# flatsat.net
KiCad netlist of a schematic drawn in EAGLE
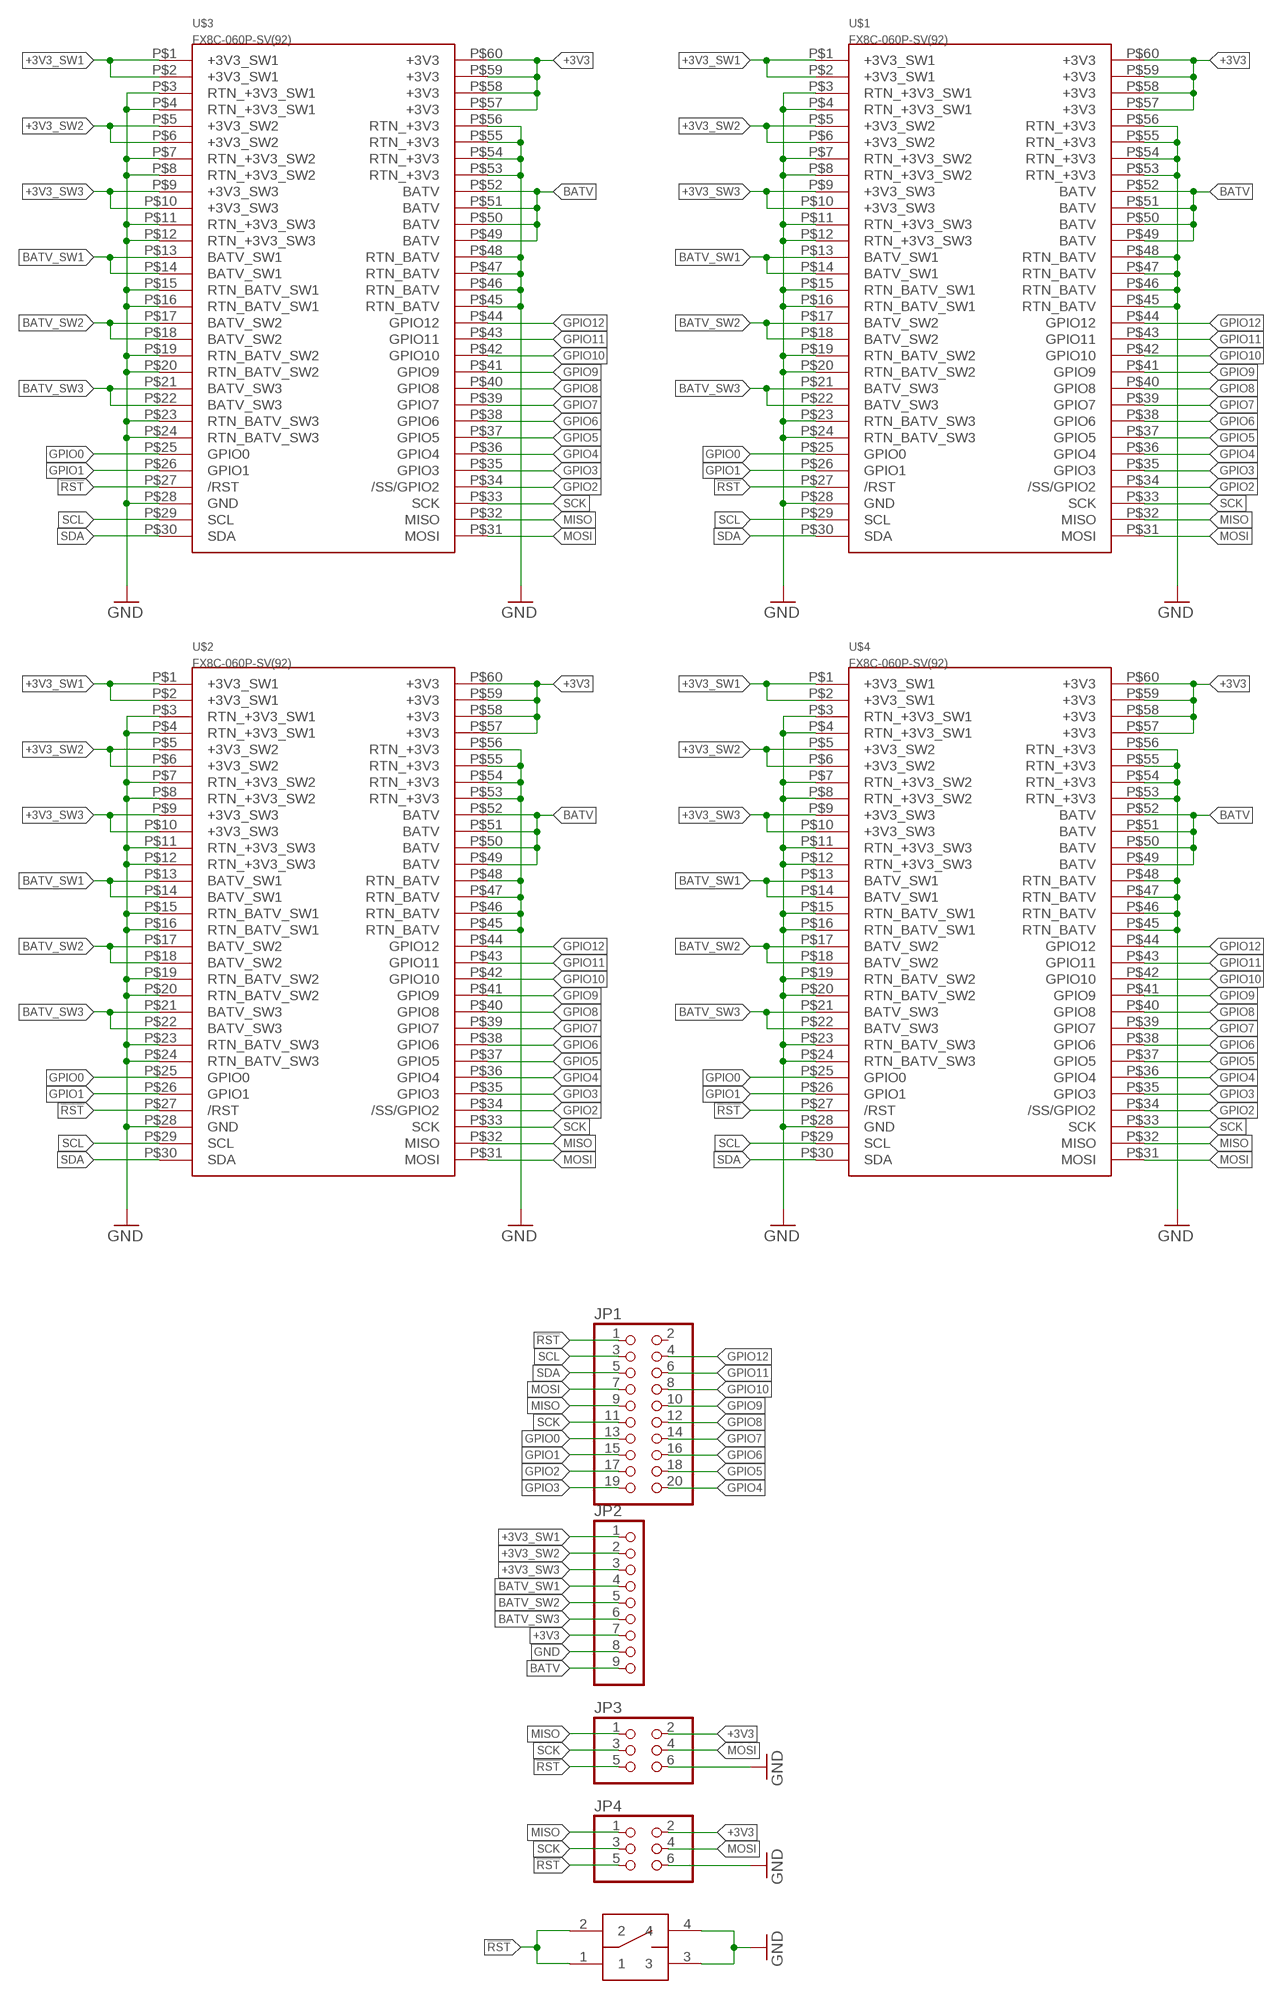
[diagram p0: schematic, sheet 1]

(export (version "E")
  (design (tool "Eeschema 10.0.6"))
  (components
    (comp (ref "JP1")
      (value "PINHD-2X10")
      (footprint "eagle-import:2X10")
      (libsource (lib "eagle-import") (part "PINHD-2X10"))
    )
    (comp (ref "JP2")
      (value "PINHD-1X9")
      (footprint "eagle-import:1X09")
      (libsource (lib "eagle-import") (part "PINHD-1X9"))
    )
    (comp (ref "JP3")
      (value "PINHD-2X3")
      (footprint "eagle-import:2X03")
      (libsource (lib "eagle-import") (part "PINHD-2X3"))
    )
    (comp (ref "JP4")
      (value "PINHD-2X3")
      (footprint "eagle-import:2X03")
      (libsource (lib "eagle-import") (part "PINHD-2X3"))
    )
    (comp (ref "U$1")
      (value "FX8C-060P-SV(92)")
      (footprint "eagle-import:FX8C-060P-SV(92)")
      (libsource (lib "eagle-import") (part "FX8C-060P-SV(92)"))
    )
    (comp (ref "U$2")
      (value "FX8C-060P-SV(92)")
      (footprint "eagle-import:FX8C-060P-SV(92)")
      (libsource (lib "eagle-import") (part "FX8C-060P-SV(92)"))
    )
    (comp (ref "U$3")
      (value "FX8C-060P-SV(92)")
      (footprint "eagle-import:FX8C-060P-SV(92)")
      (libsource (lib "eagle-import") (part "FX8C-060P-SV(92)"))
    )
    (comp (ref "U$4")
      (value "FX8C-060P-SV(92)")
      (footprint "eagle-import:FX8C-060P-SV(92)")
      (libsource (lib "eagle-import") (part "FX8C-060P-SV(92)"))
    )
    (comp (ref "U$5")
      (value "SWITCH-TL3301")
      (footprint "eagle-import:SWITCH-TL3301")
      (libsource (lib "eagle-import") (part "SWITCH-TL3301"))
    )
  )
  (nets
    (net (code "1") (name "+3V3") (class "Default")
      (node (ref "JP2") (pin "7") (pinfunction "7_7") (pintype "passive"))
      (node (ref "JP3") (pin "2") (pinfunction "2_2") (pintype "passive"))
      (node (ref "JP4") (pin "2") (pinfunction "2_2") (pintype "passive"))
      (node (ref "U$1") (pin "P$57") (pinfunction "+3V3_P$57") (pintype "power_in"))
      (node (ref "U$1") (pin "P$58") (pinfunction "+3V3_P$58") (pintype "power_in"))
      (node (ref "U$1") (pin "P$59") (pinfunction "+3V3_P$59") (pintype "power_in"))
      (node (ref "U$1") (pin "P$60") (pinfunction "+3V3_P$60") (pintype "power_in"))
      (node (ref "U$2") (pin "P$57") (pinfunction "+3V3_P$57") (pintype "power_in"))
      (node (ref "U$2") (pin "P$58") (pinfunction "+3V3_P$58") (pintype "power_in"))
      (node (ref "U$2") (pin "P$59") (pinfunction "+3V3_P$59") (pintype "power_in"))
      (node (ref "U$2") (pin "P$60") (pinfunction "+3V3_P$60") (pintype "power_in"))
      (node (ref "U$3") (pin "P$57") (pinfunction "+3V3_P$57") (pintype "power_in"))
      (node (ref "U$3") (pin "P$58") (pinfunction "+3V3_P$58") (pintype "power_in"))
      (node (ref "U$3") (pin "P$59") (pinfunction "+3V3_P$59") (pintype "power_in"))
      (node (ref "U$3") (pin "P$60") (pinfunction "+3V3_P$60") (pintype "power_in"))
      (node (ref "U$4") (pin "P$57") (pinfunction "+3V3_P$57") (pintype "power_in"))
      (node (ref "U$4") (pin "P$58") (pinfunction "+3V3_P$58") (pintype "power_in"))
      (node (ref "U$4") (pin "P$59") (pinfunction "+3V3_P$59") (pintype "power_in"))
      (node (ref "U$4") (pin "P$60") (pinfunction "+3V3_P$60") (pintype "power_in"))
    )
    (net (code "2") (name "+3V3_SW1") (class "Default")
      (node (ref "JP2") (pin "1") (pinfunction "1_1") (pintype "passive"))
      (node (ref "U$1") (pin "P$1") (pinfunction "+3V3_SW1_P$1") (pintype "power_in"))
      (node (ref "U$1") (pin "P$2") (pinfunction "+3V3_SW1_P$2") (pintype "power_in"))
      (node (ref "U$2") (pin "P$1") (pinfunction "+3V3_SW1_P$1") (pintype "power_in"))
      (node (ref "U$2") (pin "P$2") (pinfunction "+3V3_SW1_P$2") (pintype "power_in"))
      (node (ref "U$3") (pin "P$1") (pinfunction "+3V3_SW1_P$1") (pintype "power_in"))
      (node (ref "U$3") (pin "P$2") (pinfunction "+3V3_SW1_P$2") (pintype "power_in"))
      (node (ref "U$4") (pin "P$1") (pinfunction "+3V3_SW1_P$1") (pintype "power_in"))
      (node (ref "U$4") (pin "P$2") (pinfunction "+3V3_SW1_P$2") (pintype "power_in"))
    )
    (net (code "3") (name "+3V3_SW2") (class "Default")
      (node (ref "JP2") (pin "2") (pinfunction "2_2") (pintype "passive"))
      (node (ref "U$1") (pin "P$5") (pinfunction "+3V3_SW2_P$5") (pintype "power_in"))
      (node (ref "U$1") (pin "P$6") (pinfunction "+3V3_SW2_P$6") (pintype "power_in"))
      (node (ref "U$2") (pin "P$5") (pinfunction "+3V3_SW2_P$5") (pintype "power_in"))
      (node (ref "U$2") (pin "P$6") (pinfunction "+3V3_SW2_P$6") (pintype "power_in"))
      (node (ref "U$3") (pin "P$5") (pinfunction "+3V3_SW2_P$5") (pintype "power_in"))
      (node (ref "U$3") (pin "P$6") (pinfunction "+3V3_SW2_P$6") (pintype "power_in"))
      (node (ref "U$4") (pin "P$5") (pinfunction "+3V3_SW2_P$5") (pintype "power_in"))
      (node (ref "U$4") (pin "P$6") (pinfunction "+3V3_SW2_P$6") (pintype "power_in"))
    )
    (net (code "4") (name "+3V3_SW3") (class "Default")
      (node (ref "JP2") (pin "3") (pinfunction "3_3") (pintype "passive"))
      (node (ref "U$1") (pin "P$10") (pinfunction "+3V3_SW3_P$10") (pintype "power_in"))
      (node (ref "U$1") (pin "P$9") (pinfunction "+3V3_SW3_P$9") (pintype "power_in"))
      (node (ref "U$2") (pin "P$10") (pinfunction "+3V3_SW3_P$10") (pintype "power_in"))
      (node (ref "U$2") (pin "P$9") (pinfunction "+3V3_SW3_P$9") (pintype "power_in"))
      (node (ref "U$3") (pin "P$10") (pinfunction "+3V3_SW3_P$10") (pintype "power_in"))
      (node (ref "U$3") (pin "P$9") (pinfunction "+3V3_SW3_P$9") (pintype "power_in"))
      (node (ref "U$4") (pin "P$10") (pinfunction "+3V3_SW3_P$10") (pintype "power_in"))
      (node (ref "U$4") (pin "P$9") (pinfunction "+3V3_SW3_P$9") (pintype "power_in"))
    )
    (net (code "5") (name "/~{RST}") (class "Default")
      (node (ref "JP1") (pin "1") (pinfunction "1_1") (pintype "passive"))
      (node (ref "JP3") (pin "5") (pinfunction "5_5") (pintype "passive"))
      (node (ref "JP4") (pin "5") (pinfunction "5_5") (pintype "passive"))
      (node (ref "U$1") (pin "P$27") (pinfunction "/RST_P$27") (pintype "bidirectional"))
      (node (ref "U$2") (pin "P$27") (pinfunction "/RST_P$27") (pintype "bidirectional"))
      (node (ref "U$3") (pin "P$27") (pinfunction "/RST_P$27") (pintype "bidirectional"))
      (node (ref "U$4") (pin "P$27") (pinfunction "/RST_P$27") (pintype "bidirectional"))
      (node (ref "U$5") (pin "1") (pinfunction "1_1") (pintype "bidirectional"))
      (node (ref "U$5") (pin "2") (pinfunction "2_2") (pintype "bidirectional"))
    )
    (net (code "6") (name "BATV") (class "Default")
      (node (ref "JP2") (pin "9") (pinfunction "9_9") (pintype "passive"))
      (node (ref "U$1") (pin "P$49") (pinfunction "BATV_P$49") (pintype "power_in"))
      (node (ref "U$1") (pin "P$50") (pinfunction "BATV_P$50") (pintype "power_in"))
      (node (ref "U$1") (pin "P$51") (pinfunction "BATV_P$51") (pintype "power_in"))
      (node (ref "U$1") (pin "P$52") (pinfunction "BATV_P$52") (pintype "power_in"))
      (node (ref "U$2") (pin "P$49") (pinfunction "BATV_P$49") (pintype "power_in"))
      (node (ref "U$2") (pin "P$50") (pinfunction "BATV_P$50") (pintype "power_in"))
      (node (ref "U$2") (pin "P$51") (pinfunction "BATV_P$51") (pintype "power_in"))
      (node (ref "U$2") (pin "P$52") (pinfunction "BATV_P$52") (pintype "power_in"))
      (node (ref "U$3") (pin "P$49") (pinfunction "BATV_P$49") (pintype "power_in"))
      (node (ref "U$3") (pin "P$50") (pinfunction "BATV_P$50") (pintype "power_in"))
      (node (ref "U$3") (pin "P$51") (pinfunction "BATV_P$51") (pintype "power_in"))
      (node (ref "U$3") (pin "P$52") (pinfunction "BATV_P$52") (pintype "power_in"))
      (node (ref "U$4") (pin "P$49") (pinfunction "BATV_P$49") (pintype "power_in"))
      (node (ref "U$4") (pin "P$50") (pinfunction "BATV_P$50") (pintype "power_in"))
      (node (ref "U$4") (pin "P$51") (pinfunction "BATV_P$51") (pintype "power_in"))
      (node (ref "U$4") (pin "P$52") (pinfunction "BATV_P$52") (pintype "power_in"))
    )
    (net (code "7") (name "BATV_SW1") (class "Default")
      (node (ref "JP2") (pin "4") (pinfunction "4_4") (pintype "passive"))
      (node (ref "U$1") (pin "P$13") (pinfunction "BATV_SW1_P$13") (pintype "power_in"))
      (node (ref "U$1") (pin "P$14") (pinfunction "BATV_SW1_P$14") (pintype "power_in"))
      (node (ref "U$2") (pin "P$13") (pinfunction "BATV_SW1_P$13") (pintype "power_in"))
      (node (ref "U$2") (pin "P$14") (pinfunction "BATV_SW1_P$14") (pintype "power_in"))
      (node (ref "U$3") (pin "P$13") (pinfunction "BATV_SW1_P$13") (pintype "power_in"))
      (node (ref "U$3") (pin "P$14") (pinfunction "BATV_SW1_P$14") (pintype "power_in"))
      (node (ref "U$4") (pin "P$13") (pinfunction "BATV_SW1_P$13") (pintype "power_in"))
      (node (ref "U$4") (pin "P$14") (pinfunction "BATV_SW1_P$14") (pintype "power_in"))
    )
    (net (code "8") (name "BATV_SW2") (class "Default")
      (node (ref "JP2") (pin "5") (pinfunction "5_5") (pintype "passive"))
      (node (ref "U$1") (pin "P$17") (pinfunction "BATV_SW2_P$17") (pintype "power_in"))
      (node (ref "U$1") (pin "P$18") (pinfunction "BATV_SW2_P$18") (pintype "power_in"))
      (node (ref "U$2") (pin "P$17") (pinfunction "BATV_SW2_P$17") (pintype "power_in"))
      (node (ref "U$2") (pin "P$18") (pinfunction "BATV_SW2_P$18") (pintype "power_in"))
      (node (ref "U$3") (pin "P$17") (pinfunction "BATV_SW2_P$17") (pintype "power_in"))
      (node (ref "U$3") (pin "P$18") (pinfunction "BATV_SW2_P$18") (pintype "power_in"))
      (node (ref "U$4") (pin "P$17") (pinfunction "BATV_SW2_P$17") (pintype "power_in"))
      (node (ref "U$4") (pin "P$18") (pinfunction "BATV_SW2_P$18") (pintype "power_in"))
    )
    (net (code "9") (name "BATV_SW3") (class "Default")
      (node (ref "JP2") (pin "6") (pinfunction "6_6") (pintype "passive"))
      (node (ref "U$1") (pin "P$21") (pinfunction "BATV_SW3_P$21") (pintype "power_in"))
      (node (ref "U$1") (pin "P$22") (pinfunction "BATV_SW3_P$22") (pintype "power_in"))
      (node (ref "U$2") (pin "P$21") (pinfunction "BATV_SW3_P$21") (pintype "power_in"))
      (node (ref "U$2") (pin "P$22") (pinfunction "BATV_SW3_P$22") (pintype "power_in"))
      (node (ref "U$3") (pin "P$21") (pinfunction "BATV_SW3_P$21") (pintype "power_in"))
      (node (ref "U$3") (pin "P$22") (pinfunction "BATV_SW3_P$22") (pintype "power_in"))
      (node (ref "U$4") (pin "P$21") (pinfunction "BATV_SW3_P$21") (pintype "power_in"))
      (node (ref "U$4") (pin "P$22") (pinfunction "BATV_SW3_P$22") (pintype "power_in"))
    )
    (net (code "10") (name "GND") (class "Default")
      (node (ref "JP2") (pin "8") (pinfunction "8_8") (pintype "passive"))
      (node (ref "JP3") (pin "6") (pinfunction "6_6") (pintype "passive"))
      (node (ref "JP4") (pin "6") (pinfunction "6_6") (pintype "passive"))
      (node (ref "U$1") (pin "P$11") (pinfunction "RTN_+3V3_SW3_P$11") (pintype "power_in"))
      (node (ref "U$1") (pin "P$12") (pinfunction "RTN_+3V3_SW3_P$12") (pintype "power_in"))
      (node (ref "U$1") (pin "P$15") (pinfunction "RTN_BATV_SW1_P$15") (pintype "power_in"))
      (node (ref "U$1") (pin "P$16") (pinfunction "RTN_BATV_SW1_P$16") (pintype "power_in"))
      (node (ref "U$1") (pin "P$19") (pinfunction "RTN_BATV_SW2_P$19") (pintype "power_in"))
      (node (ref "U$1") (pin "P$20") (pinfunction "RTN_BATV_SW2_P$20") (pintype "power_in"))
      (node (ref "U$1") (pin "P$23") (pinfunction "RTN_BATV_SW3_P$23") (pintype "power_in"))
      (node (ref "U$1") (pin "P$24") (pinfunction "RTN_BATV_SW3_P$24") (pintype "power_in"))
      (node (ref "U$1") (pin "P$28") (pinfunction "GND_P$28") (pintype "bidirectional"))
      (node (ref "U$1") (pin "P$3") (pinfunction "RTN_+3V3_SW1_P$3") (pintype "power_in"))
      (node (ref "U$1") (pin "P$4") (pinfunction "RTN_+3V3_SW1_P$4") (pintype "power_in"))
      (node (ref "U$1") (pin "P$45") (pinfunction "RTN_BATV_P$45") (pintype "power_in"))
      (node (ref "U$1") (pin "P$46") (pinfunction "RTN_BATV_P$46") (pintype "power_in"))
      (node (ref "U$1") (pin "P$47") (pinfunction "RTN_BATV_P$47") (pintype "power_in"))
      (node (ref "U$1") (pin "P$48") (pinfunction "RTN_BATV_P$48") (pintype "power_in"))
      (node (ref "U$1") (pin "P$53") (pinfunction "RTN_+3V3_P$53") (pintype "power_in"))
      (node (ref "U$1") (pin "P$54") (pinfunction "RTN_+3V3_P$54") (pintype "power_in"))
      (node (ref "U$1") (pin "P$55") (pinfunction "RTN_+3V3_P$55") (pintype "power_in"))
      (node (ref "U$1") (pin "P$56") (pinfunction "RTN_+3V3_P$56") (pintype "power_in"))
      (node (ref "U$1") (pin "P$7") (pinfunction "RTN_+3V3_SW2_P$7") (pintype "power_in"))
      (node (ref "U$1") (pin "P$8") (pinfunction "RTN_+3V3_SW2_P$8") (pintype "power_in"))
      (node (ref "U$2") (pin "P$11") (pinfunction "RTN_+3V3_SW3_P$11") (pintype "power_in"))
      (node (ref "U$2") (pin "P$12") (pinfunction "RTN_+3V3_SW3_P$12") (pintype "power_in"))
      (node (ref "U$2") (pin "P$15") (pinfunction "RTN_BATV_SW1_P$15") (pintype "power_in"))
      (node (ref "U$2") (pin "P$16") (pinfunction "RTN_BATV_SW1_P$16") (pintype "power_in"))
      (node (ref "U$2") (pin "P$19") (pinfunction "RTN_BATV_SW2_P$19") (pintype "power_in"))
      (node (ref "U$2") (pin "P$20") (pinfunction "RTN_BATV_SW2_P$20") (pintype "power_in"))
      (node (ref "U$2") (pin "P$23") (pinfunction "RTN_BATV_SW3_P$23") (pintype "power_in"))
      (node (ref "U$2") (pin "P$24") (pinfunction "RTN_BATV_SW3_P$24") (pintype "power_in"))
      (node (ref "U$2") (pin "P$28") (pinfunction "GND_P$28") (pintype "bidirectional"))
      (node (ref "U$2") (pin "P$3") (pinfunction "RTN_+3V3_SW1_P$3") (pintype "power_in"))
      (node (ref "U$2") (pin "P$4") (pinfunction "RTN_+3V3_SW1_P$4") (pintype "power_in"))
      (node (ref "U$2") (pin "P$45") (pinfunction "RTN_BATV_P$45") (pintype "power_in"))
      (node (ref "U$2") (pin "P$46") (pinfunction "RTN_BATV_P$46") (pintype "power_in"))
      (node (ref "U$2") (pin "P$47") (pinfunction "RTN_BATV_P$47") (pintype "power_in"))
      (node (ref "U$2") (pin "P$48") (pinfunction "RTN_BATV_P$48") (pintype "power_in"))
      (node (ref "U$2") (pin "P$53") (pinfunction "RTN_+3V3_P$53") (pintype "power_in"))
      (node (ref "U$2") (pin "P$54") (pinfunction "RTN_+3V3_P$54") (pintype "power_in"))
      (node (ref "U$2") (pin "P$55") (pinfunction "RTN_+3V3_P$55") (pintype "power_in"))
      (node (ref "U$2") (pin "P$56") (pinfunction "RTN_+3V3_P$56") (pintype "power_in"))
      (node (ref "U$2") (pin "P$7") (pinfunction "RTN_+3V3_SW2_P$7") (pintype "power_in"))
      (node (ref "U$2") (pin "P$8") (pinfunction "RTN_+3V3_SW2_P$8") (pintype "power_in"))
      (node (ref "U$3") (pin "P$11") (pinfunction "RTN_+3V3_SW3_P$11") (pintype "power_in"))
      (node (ref "U$3") (pin "P$12") (pinfunction "RTN_+3V3_SW3_P$12") (pintype "power_in"))
      (node (ref "U$3") (pin "P$15") (pinfunction "RTN_BATV_SW1_P$15") (pintype "power_in"))
      (node (ref "U$3") (pin "P$16") (pinfunction "RTN_BATV_SW1_P$16") (pintype "power_in"))
      (node (ref "U$3") (pin "P$19") (pinfunction "RTN_BATV_SW2_P$19") (pintype "power_in"))
      (node (ref "U$3") (pin "P$20") (pinfunction "RTN_BATV_SW2_P$20") (pintype "power_in"))
      (node (ref "U$3") (pin "P$23") (pinfunction "RTN_BATV_SW3_P$23") (pintype "power_in"))
      (node (ref "U$3") (pin "P$24") (pinfunction "RTN_BATV_SW3_P$24") (pintype "power_in"))
      (node (ref "U$3") (pin "P$28") (pinfunction "GND_P$28") (pintype "bidirectional"))
      (node (ref "U$3") (pin "P$3") (pinfunction "RTN_+3V3_SW1_P$3") (pintype "power_in"))
      (node (ref "U$3") (pin "P$4") (pinfunction "RTN_+3V3_SW1_P$4") (pintype "power_in"))
      (node (ref "U$3") (pin "P$45") (pinfunction "RTN_BATV_P$45") (pintype "power_in"))
      (node (ref "U$3") (pin "P$46") (pinfunction "RTN_BATV_P$46") (pintype "power_in"))
      (node (ref "U$3") (pin "P$47") (pinfunction "RTN_BATV_P$47") (pintype "power_in"))
      (node (ref "U$3") (pin "P$48") (pinfunction "RTN_BATV_P$48") (pintype "power_in"))
      (node (ref "U$3") (pin "P$53") (pinfunction "RTN_+3V3_P$53") (pintype "power_in"))
      (node (ref "U$3") (pin "P$54") (pinfunction "RTN_+3V3_P$54") (pintype "power_in"))
      (node (ref "U$3") (pin "P$55") (pinfunction "RTN_+3V3_P$55") (pintype "power_in"))
      (node (ref "U$3") (pin "P$56") (pinfunction "RTN_+3V3_P$56") (pintype "power_in"))
      (node (ref "U$3") (pin "P$7") (pinfunction "RTN_+3V3_SW2_P$7") (pintype "power_in"))
      (node (ref "U$3") (pin "P$8") (pinfunction "RTN_+3V3_SW2_P$8") (pintype "power_in"))
      (node (ref "U$4") (pin "P$11") (pinfunction "RTN_+3V3_SW3_P$11") (pintype "power_in"))
      (node (ref "U$4") (pin "P$12") (pinfunction "RTN_+3V3_SW3_P$12") (pintype "power_in"))
      (node (ref "U$4") (pin "P$15") (pinfunction "RTN_BATV_SW1_P$15") (pintype "power_in"))
      (node (ref "U$4") (pin "P$16") (pinfunction "RTN_BATV_SW1_P$16") (pintype "power_in"))
      (node (ref "U$4") (pin "P$19") (pinfunction "RTN_BATV_SW2_P$19") (pintype "power_in"))
      (node (ref "U$4") (pin "P$20") (pinfunction "RTN_BATV_SW2_P$20") (pintype "power_in"))
      (node (ref "U$4") (pin "P$23") (pinfunction "RTN_BATV_SW3_P$23") (pintype "power_in"))
      (node (ref "U$4") (pin "P$24") (pinfunction "RTN_BATV_SW3_P$24") (pintype "power_in"))
      (node (ref "U$4") (pin "P$28") (pinfunction "GND_P$28") (pintype "bidirectional"))
      (node (ref "U$4") (pin "P$3") (pinfunction "RTN_+3V3_SW1_P$3") (pintype "power_in"))
      (node (ref "U$4") (pin "P$4") (pinfunction "RTN_+3V3_SW1_P$4") (pintype "power_in"))
      (node (ref "U$4") (pin "P$45") (pinfunction "RTN_BATV_P$45") (pintype "power_in"))
      (node (ref "U$4") (pin "P$46") (pinfunction "RTN_BATV_P$46") (pintype "power_in"))
      (node (ref "U$4") (pin "P$47") (pinfunction "RTN_BATV_P$47") (pintype "power_in"))
      (node (ref "U$4") (pin "P$48") (pinfunction "RTN_BATV_P$48") (pintype "power_in"))
      (node (ref "U$4") (pin "P$53") (pinfunction "RTN_+3V3_P$53") (pintype "power_in"))
      (node (ref "U$4") (pin "P$54") (pinfunction "RTN_+3V3_P$54") (pintype "power_in"))
      (node (ref "U$4") (pin "P$55") (pinfunction "RTN_+3V3_P$55") (pintype "power_in"))
      (node (ref "U$4") (pin "P$56") (pinfunction "RTN_+3V3_P$56") (pintype "power_in"))
      (node (ref "U$4") (pin "P$7") (pinfunction "RTN_+3V3_SW2_P$7") (pintype "power_in"))
      (node (ref "U$4") (pin "P$8") (pinfunction "RTN_+3V3_SW2_P$8") (pintype "power_in"))
      (node (ref "U$5") (pin "3") (pinfunction "3_3") (pintype "bidirectional"))
      (node (ref "U$5") (pin "4") (pinfunction "4_4") (pintype "bidirectional"))
    )
    (net (code "11") (name "GPIO0") (class "Default")
      (node (ref "JP1") (pin "13") (pinfunction "13_13") (pintype "passive"))
      (node (ref "U$1") (pin "P$25") (pinfunction "GPIO0_P$25") (pintype "bidirectional"))
      (node (ref "U$2") (pin "P$25") (pinfunction "GPIO0_P$25") (pintype "bidirectional"))
      (node (ref "U$3") (pin "P$25") (pinfunction "GPIO0_P$25") (pintype "bidirectional"))
      (node (ref "U$4") (pin "P$25") (pinfunction "GPIO0_P$25") (pintype "bidirectional"))
    )
    (net (code "12") (name "GPIO1") (class "Default")
      (node (ref "JP1") (pin "15") (pinfunction "15_15") (pintype "passive"))
      (node (ref "U$1") (pin "P$26") (pinfunction "GPIO1_P$26") (pintype "bidirectional"))
      (node (ref "U$2") (pin "P$26") (pinfunction "GPIO1_P$26") (pintype "bidirectional"))
      (node (ref "U$3") (pin "P$26") (pinfunction "GPIO1_P$26") (pintype "bidirectional"))
      (node (ref "U$4") (pin "P$26") (pinfunction "GPIO1_P$26") (pintype "bidirectional"))
    )
    (net (code "13") (name "GPIO2") (class "Default")
      (node (ref "JP1") (pin "17") (pinfunction "17_17") (pintype "passive"))
      (node (ref "U$1") (pin "P$34") (pinfunction "/SS/GPIO2_P$34") (pintype "bidirectional"))
      (node (ref "U$2") (pin "P$34") (pinfunction "/SS/GPIO2_P$34") (pintype "bidirectional"))
      (node (ref "U$3") (pin "P$34") (pinfunction "/SS/GPIO2_P$34") (pintype "bidirectional"))
      (node (ref "U$4") (pin "P$34") (pinfunction "/SS/GPIO2_P$34") (pintype "bidirectional"))
    )
    (net (code "14") (name "GPIO3") (class "Default")
      (node (ref "JP1") (pin "19") (pinfunction "19_19") (pintype "passive"))
      (node (ref "U$1") (pin "P$35") (pinfunction "GPIO3_P$35") (pintype "bidirectional"))
      (node (ref "U$2") (pin "P$35") (pinfunction "GPIO3_P$35") (pintype "bidirectional"))
      (node (ref "U$3") (pin "P$35") (pinfunction "GPIO3_P$35") (pintype "bidirectional"))
      (node (ref "U$4") (pin "P$35") (pinfunction "GPIO3_P$35") (pintype "bidirectional"))
    )
    (net (code "15") (name "GPIO4") (class "Default")
      (node (ref "JP1") (pin "20") (pinfunction "20_20") (pintype "passive"))
      (node (ref "U$1") (pin "P$36") (pinfunction "GPIO4_P$36") (pintype "bidirectional"))
      (node (ref "U$2") (pin "P$36") (pinfunction "GPIO4_P$36") (pintype "bidirectional"))
      (node (ref "U$3") (pin "P$36") (pinfunction "GPIO4_P$36") (pintype "bidirectional"))
      (node (ref "U$4") (pin "P$36") (pinfunction "GPIO4_P$36") (pintype "bidirectional"))
    )
    (net (code "16") (name "GPIO5") (class "Default")
      (node (ref "JP1") (pin "18") (pinfunction "18_18") (pintype "passive"))
      (node (ref "U$1") (pin "P$37") (pinfunction "GPIO5_P$37") (pintype "bidirectional"))
      (node (ref "U$2") (pin "P$37") (pinfunction "GPIO5_P$37") (pintype "bidirectional"))
      (node (ref "U$3") (pin "P$37") (pinfunction "GPIO5_P$37") (pintype "bidirectional"))
      (node (ref "U$4") (pin "P$37") (pinfunction "GPIO5_P$37") (pintype "bidirectional"))
    )
    (net (code "17") (name "GPIO6") (class "Default")
      (node (ref "JP1") (pin "16") (pinfunction "16_16") (pintype "passive"))
      (node (ref "U$1") (pin "P$38") (pinfunction "GPIO6_P$38") (pintype "bidirectional"))
      (node (ref "U$2") (pin "P$38") (pinfunction "GPIO6_P$38") (pintype "bidirectional"))
      (node (ref "U$3") (pin "P$38") (pinfunction "GPIO6_P$38") (pintype "bidirectional"))
      (node (ref "U$4") (pin "P$38") (pinfunction "GPIO6_P$38") (pintype "bidirectional"))
    )
    (net (code "18") (name "GPIO7") (class "Default")
      (node (ref "JP1") (pin "14") (pinfunction "14_14") (pintype "passive"))
      (node (ref "U$1") (pin "P$39") (pinfunction "GPIO7_P$39") (pintype "bidirectional"))
      (node (ref "U$2") (pin "P$39") (pinfunction "GPIO7_P$39") (pintype "bidirectional"))
      (node (ref "U$3") (pin "P$39") (pinfunction "GPIO7_P$39") (pintype "bidirectional"))
      (node (ref "U$4") (pin "P$39") (pinfunction "GPIO7_P$39") (pintype "bidirectional"))
    )
    (net (code "19") (name "GPIO8") (class "Default")
      (node (ref "JP1") (pin "12") (pinfunction "12_12") (pintype "passive"))
      (node (ref "U$1") (pin "P$40") (pinfunction "GPIO8_P$40") (pintype "bidirectional"))
      (node (ref "U$2") (pin "P$40") (pinfunction "GPIO8_P$40") (pintype "bidirectional"))
      (node (ref "U$3") (pin "P$40") (pinfunction "GPIO8_P$40") (pintype "bidirectional"))
      (node (ref "U$4") (pin "P$40") (pinfunction "GPIO8_P$40") (pintype "bidirectional"))
    )
    (net (code "20") (name "GPIO9") (class "Default")
      (node (ref "JP1") (pin "10") (pinfunction "10_10") (pintype "passive"))
      (node (ref "U$1") (pin "P$41") (pinfunction "GPIO9_P$41") (pintype "bidirectional"))
      (node (ref "U$2") (pin "P$41") (pinfunction "GPIO9_P$41") (pintype "bidirectional"))
      (node (ref "U$3") (pin "P$41") (pinfunction "GPIO9_P$41") (pintype "bidirectional"))
      (node (ref "U$4") (pin "P$41") (pinfunction "GPIO9_P$41") (pintype "bidirectional"))
    )
    (net (code "21") (name "GPIO10") (class "Default")
      (node (ref "JP1") (pin "8") (pinfunction "8_8") (pintype "passive"))
      (node (ref "U$1") (pin "P$42") (pinfunction "GPIO10_P$42") (pintype "bidirectional"))
      (node (ref "U$2") (pin "P$42") (pinfunction "GPIO10_P$42") (pintype "bidirectional"))
      (node (ref "U$3") (pin "P$42") (pinfunction "GPIO10_P$42") (pintype "bidirectional"))
      (node (ref "U$4") (pin "P$42") (pinfunction "GPIO10_P$42") (pintype "bidirectional"))
    )
    (net (code "22") (name "GPIO11") (class "Default")
      (node (ref "JP1") (pin "6") (pinfunction "6_6") (pintype "passive"))
      (node (ref "U$1") (pin "P$43") (pinfunction "GPIO11_P$43") (pintype "bidirectional"))
      (node (ref "U$2") (pin "P$43") (pinfunction "GPIO11_P$43") (pintype "bidirectional"))
      (node (ref "U$3") (pin "P$43") (pinfunction "GPIO11_P$43") (pintype "bidirectional"))
      (node (ref "U$4") (pin "P$43") (pinfunction "GPIO11_P$43") (pintype "bidirectional"))
    )
    (net (code "23") (name "GPIO12") (class "Default")
      (node (ref "JP1") (pin "4") (pinfunction "4_4") (pintype "passive"))
      (node (ref "U$1") (pin "P$44") (pinfunction "GPIO12_P$44") (pintype "bidirectional"))
      (node (ref "U$2") (pin "P$44") (pinfunction "GPIO12_P$44") (pintype "bidirectional"))
      (node (ref "U$3") (pin "P$44") (pinfunction "GPIO12_P$44") (pintype "bidirectional"))
      (node (ref "U$4") (pin "P$44") (pinfunction "GPIO12_P$44") (pintype "bidirectional"))
    )
    (net (code "24") (name "MISO") (class "Default")
      (node (ref "JP1") (pin "9") (pinfunction "9_9") (pintype "passive"))
      (node (ref "JP3") (pin "1") (pinfunction "1_1") (pintype "passive"))
      (node (ref "JP4") (pin "1") (pinfunction "1_1") (pintype "passive"))
      (node (ref "U$1") (pin "P$32") (pinfunction "MISO_P$32") (pintype "bidirectional"))
      (node (ref "U$2") (pin "P$32") (pinfunction "MISO_P$32") (pintype "bidirectional"))
      (node (ref "U$3") (pin "P$32") (pinfunction "MISO_P$32") (pintype "bidirectional"))
      (node (ref "U$4") (pin "P$32") (pinfunction "MISO_P$32") (pintype "bidirectional"))
    )
    (net (code "25") (name "MOSI") (class "Default")
      (node (ref "JP1") (pin "7") (pinfunction "7_7") (pintype "passive"))
      (node (ref "JP3") (pin "4") (pinfunction "4_4") (pintype "passive"))
      (node (ref "JP4") (pin "4") (pinfunction "4_4") (pintype "passive"))
      (node (ref "U$1") (pin "P$31") (pinfunction "MOSI_P$31") (pintype "bidirectional"))
      (node (ref "U$2") (pin "P$31") (pinfunction "MOSI_P$31") (pintype "bidirectional"))
      (node (ref "U$3") (pin "P$31") (pinfunction "MOSI_P$31") (pintype "bidirectional"))
      (node (ref "U$4") (pin "P$31") (pinfunction "MOSI_P$31") (pintype "bidirectional"))
    )
    (net (code "26") (name "SCK") (class "Default")
      (node (ref "JP1") (pin "11") (pinfunction "11_11") (pintype "passive"))
      (node (ref "JP3") (pin "3") (pinfunction "3_3") (pintype "passive"))
      (node (ref "JP4") (pin "3") (pinfunction "3_3") (pintype "passive"))
      (node (ref "U$1") (pin "P$33") (pinfunction "SCK_P$33") (pintype "bidirectional"))
      (node (ref "U$2") (pin "P$33") (pinfunction "SCK_P$33") (pintype "bidirectional"))
      (node (ref "U$3") (pin "P$33") (pinfunction "SCK_P$33") (pintype "bidirectional"))
      (node (ref "U$4") (pin "P$33") (pinfunction "SCK_P$33") (pintype "bidirectional"))
    )
    (net (code "27") (name "SCL") (class "Default")
      (node (ref "JP1") (pin "3") (pinfunction "3_3") (pintype "passive"))
      (node (ref "U$1") (pin "P$29") (pinfunction "SCL_P$29") (pintype "bidirectional"))
      (node (ref "U$2") (pin "P$29") (pinfunction "SCL_P$29") (pintype "bidirectional"))
      (node (ref "U$3") (pin "P$29") (pinfunction "SCL_P$29") (pintype "bidirectional"))
      (node (ref "U$4") (pin "P$29") (pinfunction "SCL_P$29") (pintype "bidirectional"))
    )
    (net (code "28") (name "SDA") (class "Default")
      (node (ref "JP1") (pin "5") (pinfunction "5_5") (pintype "passive"))
      (node (ref "U$1") (pin "P$30") (pinfunction "SDA_P$30") (pintype "bidirectional"))
      (node (ref "U$2") (pin "P$30") (pinfunction "SDA_P$30") (pintype "bidirectional"))
      (node (ref "U$3") (pin "P$30") (pinfunction "SDA_P$30") (pintype "bidirectional"))
      (node (ref "U$4") (pin "P$30") (pinfunction "SDA_P$30") (pintype "bidirectional"))
    )
    (net (code "29") (name "unconnected-(JP1-Pad2)") (class "Default")
      (node (ref "JP1") (pin "2") (pinfunction "2_2") (pintype "passive"))
    )
  )
)
